# 5v_power_supply.net
KiCad netlist of a schematic drawn in EAGLE
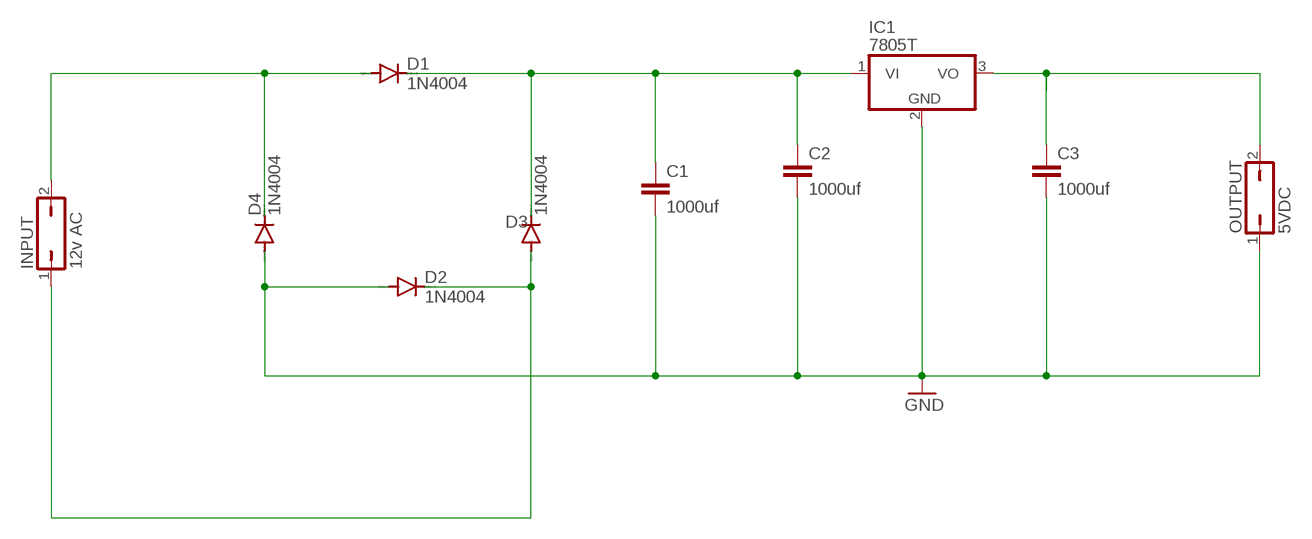
[diagram p0: schematic, sheet 1]

(export (version "E")
  (design (tool "Eeschema 10.0.6"))
  (components
    (comp (ref "C1")
      (value "1000uf")
      (footprint "eagle-import:C2.5-3")
      (libsource (lib "eagle-import") (part "C2,5-3"))
    )
    (comp (ref "C2")
      (value "1000uf")
      (footprint "eagle-import:C2.5-3")
      (libsource (lib "eagle-import") (part "C2,5-3"))
    )
    (comp (ref "C3")
      (value "1000uf")
      (footprint "eagle-import:C2.5-3")
      (libsource (lib "eagle-import") (part "C2,5-3"))
    )
    (comp (ref "D1")
      (value "1N4004")
      (footprint "eagle-import:DO41-10")
      (libsource (lib "eagle-import") (part "1N4004"))
    )
    (comp (ref "D2")
      (value "1N4004")
      (footprint "eagle-import:DO41-10")
      (libsource (lib "eagle-import") (part "1N4004"))
    )
    (comp (ref "D3")
      (value "1N4004")
      (footprint "eagle-import:DO41-10")
      (libsource (lib "eagle-import") (part "1N4004"))
    )
    (comp (ref "D4")
      (value "1N4004")
      (footprint "eagle-import:DO41-10")
      (libsource (lib "eagle-import") (part "1N4004"))
    )
    (comp (ref "IC1")
      (value "7805T")
      (footprint "eagle-import:TO220H")
      (libsource (lib "eagle-import") (part "78T05"))
    )
    (comp (ref "INPUT")
      (value "12v AC")
      (footprint "eagle-import:JP1")
      (libsource (lib "eagle-import") (part "JP1Q"))
    )
    (comp (ref "OUTPUT")
      (value "5VDC")
      (footprint "eagle-import:JP1")
      (libsource (lib "eagle-import") (part "JP1Q"))
    )
  )
  (nets
    (net (code "1") (name "GND") (class "Default")
      (node (ref "C1") (pin "2") (pinfunction "2_2") (pintype "passive"))
      (node (ref "C2") (pin "2") (pinfunction "2_2") (pintype "passive"))
      (node (ref "C3") (pin "2") (pinfunction "2_2") (pintype "passive"))
      (node (ref "D2") (pin "A") (pinfunction "A_A") (pintype "passive"))
      (node (ref "D4") (pin "A") (pinfunction "A_A") (pintype "passive"))
      (node (ref "IC1") (pin "2") (pinfunction "GND_2") (pintype "passive"))
      (node (ref "OUTPUT") (pin "1") (pinfunction "1_1") (pintype "passive"))
    )
    (net (code "2") (name "Net-(D1-PadA)") (class "Default")
      (node (ref "D1") (pin "A") (pinfunction "A_A") (pintype "passive"))
      (node (ref "D4") (pin "C") (pinfunction "C_C") (pintype "passive"))
      (node (ref "INPUT") (pin "2") (pinfunction "2_2") (pintype "passive"))
    )
    (net (code "3") (name "Net-(D2-PadC)") (class "Default")
      (node (ref "D2") (pin "C") (pinfunction "C_C") (pintype "passive"))
      (node (ref "D3") (pin "A") (pinfunction "A_A") (pintype "passive"))
      (node (ref "INPUT") (pin "1") (pinfunction "1_1") (pintype "passive"))
    )
    (net (code "4") (name "Net-(IC1-VI)") (class "Default")
      (node (ref "C1") (pin "1") (pinfunction "1_1") (pintype "passive"))
      (node (ref "C2") (pin "1") (pinfunction "1_1") (pintype "passive"))
      (node (ref "D1") (pin "C") (pinfunction "C_C") (pintype "passive"))
      (node (ref "D3") (pin "C") (pinfunction "C_C") (pintype "passive"))
      (node (ref "IC1") (pin "1") (pinfunction "VI_1") (pintype "input"))
    )
    (net (code "5") (name "Net-(IC1-VO)") (class "Default")
      (node (ref "C3") (pin "1") (pinfunction "1_1") (pintype "passive"))
      (node (ref "IC1") (pin "3") (pinfunction "VO_3") (pintype "passive"))
      (node (ref "OUTPUT") (pin "2") (pinfunction "2_2") (pintype "passive"))
    )
  )
)
